# SWD2TC.net
KiCad netlist of a schematic drawn in EAGLE
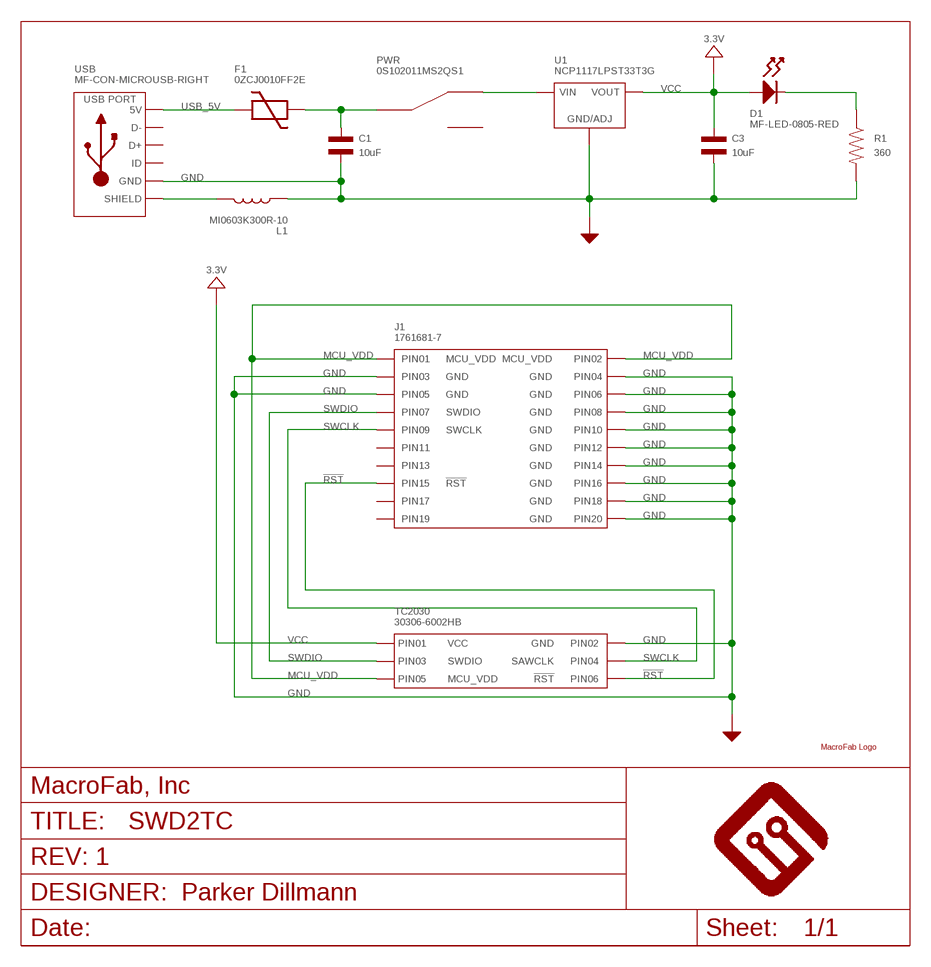
[diagram p0: schematic, sheet 1]

(export (version "E")
  (design (tool "Eeschema 10.0.6"))
  (components
    (comp (ref "C1")
      (value "10uF")
      (footprint "eagle-import:C1206")
      (fields (field (name "MPN") "MF-CAP-1206-10uF"))
      (libsource (lib "eagle-import") (part "CAPACITOR_NP_1206"))
    )
    (comp (ref "C3")
      (value "10uF")
      (footprint "eagle-import:C1206")
      (fields (field (name "MPN") "MF-CAP-1206-10uF"))
      (libsource (lib "eagle-import") (part "CAPACITOR_NP_1206"))
    )
    (comp (ref "D1")
      (value "MF-LED-0805-RED")
      (footprint "eagle-import:LED0805")
      (fields (field (name "HOUSEPART") "YES"))
      (libsource (lib "eagle-import") (part "LED_SINGLE-0805-RED"))
    )
    (comp (ref "F1")
      (value "0ZCJ0010FF2E")
      (footprint "eagle-import:1206")
      (libsource (lib "eagle-import") (part "PTC_FUSE_1206"))
    )
    (comp (ref "FRAME1")
      (value "MF_FRAMEDEFAULT")
      (footprint "eagle-import:MF_FRAME_DEFAULT")
      (fields
        (field (name "HOUSEPART") "0")
        (field (name "DNAME") "Parker Dillmann")
        (field (name "REVNUM") "REV: 1")
      )
      (libsource (lib "eagle-import") (part "MF_FRAMEDEFAULT"))
    )
    (comp (ref "J1")
      (value "1761681-7")
      (footprint "eagle-import:1761681-7")
      (fields
        (field (name "LABEL01") "MCU_VDD")
        (field (name "LABEL02") "MCU_VDD")
        (field (name "LABEL03") "GND")
        (field (name "LABEL04") "GND")
        (field (name "LABEL05") "GND")
        (field (name "LABEL06") "GND")
        (field (name "LABEL07") "SWDIO")
        (field (name "LABEL08") "GND")
        (field (name "LABEL09") "SWCLK")
        (field (name "LABEL10") "GND")
        (field (name "LABEL12") "GND")
        (field (name "LABEL14") "GND")
        (field (name "LABEL15") "!RST")
        (field (name "LABEL16") "GND")
        (field (name "LABEL18") "GND")
        (field (name "LABEL20") "GND")
      )
      (libsource (lib "eagle-import") (part "CON_02X10_1761681-7"))
    )
    (comp (ref "L1")
      (value "MI0603K300R-10")
      (footprint "eagle-import:L0603")
      (fields (field (name "MPN") "MI0603K300R-10"))
      (libsource (lib "eagle-import") (part "INDUCTOR_0603"))
    )
    (comp (ref "PWR")
      (value "0S102011MS2QS1")
      (footprint "eagle-import:0S102011MS2QS1")
      (libsource (lib "eagle-import") (part "SPDT_0S102011MS2QS1"))
    )
    (comp (ref "R1")
      (value "360")
      (footprint "eagle-import:R0805")
      (fields (field (name "MPN") "MF-RES-0805-360"))
      (libsource (lib "eagle-import") (part "RESISTOR_0805"))
    )
    (comp (ref "TC2030")
      (value "30306-6002HB")
      (footprint "eagle-import:30306-6002HB")
      (fields
        (field (name "LABEL01") "VCC")
        (field (name "LABEL02") "GND")
        (field (name "LABEL03") "SWDIO")
        (field (name "LABEL04") "SAWCLK")
        (field (name "LABEL05") "MCU_VDD")
        (field (name "LABEL06") "!RST")
      )
      (libsource (lib "eagle-import") (part "CON_02X03_30306-6002HB"))
    )
    (comp (ref "U$3")
      (value "MF_LOGOLOGO_MEDIUM")
      (footprint "eagle-import:MF_LOGO_MEDIUM")
      (libsource (lib "eagle-import") (part "MF_LOGOLOGO_MEDIUM"))
    )
    (comp (ref "U1")
      (value "NCP1117LPST33T3G")
      (footprint "eagle-import:SOT-223-3")
      (fields (field (name "HOUSEPART") "NO"))
      (libsource (lib "eagle-import") (part "NCP1117LPST33T3G"))
    )
    (comp (ref "USB")
      (value "MF-CON-MICROUSB-RIGHT")
      (footprint "eagle-import:MICROUSB-RIGHT")
      (fields (field (name "HOUSEPART") "YES"))
      (libsource (lib "eagle-import") (part "USB_MICRO_RIGHT"))
    )
  )
  (nets
    (net (code "1") (name "/MCU_VDD") (class "Default")
      (node (ref "J1") (pin "P$1") (pinfunction "1_P$1") (pintype "bidirectional"))
      (node (ref "J1") (pin "P$2") (pinfunction "2_P$2") (pintype "bidirectional"))
      (node (ref "TC2030") (pin "5") (pinfunction "PIN5_5") (pintype "bidirectional"))
    )
    (net (code "2") (name "/SWCLK") (class "Default")
      (node (ref "J1") (pin "P$9") (pinfunction "9_P$9") (pintype "bidirectional"))
      (node (ref "TC2030") (pin "4") (pinfunction "PIN4_4") (pintype "bidirectional"))
    )
    (net (code "3") (name "/SWDIO") (class "Default")
      (node (ref "J1") (pin "P$7") (pinfunction "7_P$7") (pintype "bidirectional"))
      (node (ref "TC2030") (pin "3") (pinfunction "PIN3_3") (pintype "bidirectional"))
    )
    (net (code "4") (name "/USB_5V") (class "Default")
      (node (ref "F1") (pin "1") (pinfunction "P$1_1") (pintype "bidirectional"))
      (node (ref "USB") (pin "1") (pinfunction "5V_1") (pintype "power_in"))
    )
    (net (code "5") (name "/~{RST}") (class "Default")
      (node (ref "J1") (pin "P$15") (pinfunction "15_P$15") (pintype "bidirectional"))
      (node (ref "TC2030") (pin "6") (pinfunction "PIN6_6") (pintype "bidirectional"))
    )
    (net (code "6") (name "3.3V") (class "Default")
      (node (ref "C3") (pin "P$1") (pinfunction "P$1_P$1") (pintype "passive"))
      (node (ref "D1") (pin "ANODE") (pinfunction "ANODE_ANODE") (pintype "power_in"))
      (node (ref "TC2030") (pin "1") (pinfunction "PIN1_1") (pintype "bidirectional"))
      (node (ref "U1") (pin "P$1") (pinfunction "VOUT_P$1") (pintype "bidirectional"))
      (node (ref "U1") (pin "P$3") (pinfunction "VOUT_P$3") (pintype "bidirectional"))
    )
    (net (code "7") (name "GND_RAIL") (class "Default")
      (node (ref "C1") (pin "P$2") (pinfunction "P$2_P$2") (pintype "passive"))
      (node (ref "C3") (pin "P$2") (pinfunction "P$2_P$2") (pintype "passive"))
      (node (ref "J1") (pin "P$10") (pinfunction "10_P$10") (pintype "bidirectional"))
      (node (ref "J1") (pin "P$12") (pinfunction "12_P$12") (pintype "bidirectional"))
      (node (ref "J1") (pin "P$14") (pinfunction "14_P$14") (pintype "bidirectional"))
      (node (ref "J1") (pin "P$16") (pinfunction "16_P$16") (pintype "bidirectional"))
      (node (ref "J1") (pin "P$18") (pinfunction "18_P$18") (pintype "bidirectional"))
      (node (ref "J1") (pin "P$20") (pinfunction "20_P$20") (pintype "bidirectional"))
      (node (ref "J1") (pin "P$3") (pinfunction "3_P$3") (pintype "bidirectional"))
      (node (ref "J1") (pin "P$4") (pinfunction "4_P$4") (pintype "bidirectional"))
      (node (ref "J1") (pin "P$5") (pinfunction "5_P$5") (pintype "bidirectional"))
      (node (ref "J1") (pin "P$6") (pinfunction "6_P$6") (pintype "bidirectional"))
      (node (ref "J1") (pin "P$8") (pinfunction "8_P$8") (pintype "bidirectional"))
      (node (ref "L1") (pin "P$1") (pinfunction "P$1_P$1") (pintype "passive"))
      (node (ref "R1") (pin "P$2") (pinfunction "P$2_P$2") (pintype "passive"))
      (node (ref "TC2030") (pin "2") (pinfunction "PIN2_2") (pintype "bidirectional"))
      (node (ref "U1") (pin "P$2") (pinfunction "GND/ADJ_P$2") (pintype "bidirectional"))
      (node (ref "USB") (pin "5") (pinfunction "GND_5") (pintype "power_in"))
    )
    (net (code "8") (name "Net-(D1-PadCATHODE)") (class "Default")
      (node (ref "D1") (pin "CATHODE") (pinfunction "CATHODE_CATHODE") (pintype "power_in"))
      (node (ref "R1") (pin "P$1") (pinfunction "P$1_P$1") (pintype "passive"))
    )
    (net (code "9") (name "Net-(F1-P$2)") (class "Default")
      (node (ref "C1") (pin "P$1") (pinfunction "P$1_P$1") (pintype "passive"))
      (node (ref "F1") (pin "2") (pinfunction "P$2_2") (pintype "bidirectional"))
      (node (ref "PWR") (pin "2") (pinfunction "C_2") (pintype "bidirectional"))
    )
    (net (code "10") (name "Net-(L1-PadP$2)") (class "Default")
      (node (ref "L1") (pin "P$2") (pinfunction "P$2_P$2") (pintype "passive"))
      (node (ref "USB") (pin "S1") (pinfunction "SLD_S1") (pintype "power_in"))
      (node (ref "USB") (pin "S2") (pinfunction "SLD_S2") (pintype "power_in"))
      (node (ref "USB") (pin "S3") (pinfunction "SLD_S3") (pintype "power_in"))
      (node (ref "USB") (pin "S4") (pinfunction "SLD_S4") (pintype "power_in"))
      (node (ref "USB") (pin "S5") (pinfunction "SLD_S5") (pintype "power_in"))
      (node (ref "USB") (pin "S6") (pinfunction "SLD_S6") (pintype "power_in"))
    )
    (net (code "11") (name "Net-(U1-VIN)") (class "Default")
      (node (ref "PWR") (pin "1") (pinfunction "1_1") (pintype "bidirectional"))
      (node (ref "U1") (pin "P$4") (pinfunction "VIN_P$4") (pintype "bidirectional"))
    )
    (net (code "12") (name "unconnected-(J1-11-PadP$11)") (class "Default")
      (node (ref "J1") (pin "P$11") (pinfunction "11_P$11") (pintype "bidirectional"))
    )
    (net (code "13") (name "unconnected-(J1-13-PadP$13)") (class "Default")
      (node (ref "J1") (pin "P$13") (pinfunction "13_P$13") (pintype "bidirectional"))
    )
    (net (code "14") (name "unconnected-(J1-17-PadP$17)") (class "Default")
      (node (ref "J1") (pin "P$17") (pinfunction "17_P$17") (pintype "bidirectional"))
    )
    (net (code "15") (name "unconnected-(J1-19-PadP$19)") (class "Default")
      (node (ref "J1") (pin "P$19") (pinfunction "19_P$19") (pintype "bidirectional"))
    )
    (net (code "16") (name "unconnected-(PWR-2-Pad3)") (class "Default")
      (node (ref "PWR") (pin "3") (pinfunction "2_3") (pintype "bidirectional"))
    )
    (net (code "17") (name "unconnected-(USB-D+-Pad3)") (class "Default")
      (node (ref "USB") (pin "3") (pinfunction "D+_3") (pintype "bidirectional"))
    )
    (net (code "18") (name "unconnected-(USB-D--Pad2)") (class "Default")
      (node (ref "USB") (pin "2") (pinfunction "D-_2") (pintype "bidirectional"))
    )
    (net (code "19") (name "unconnected-(USB-ID-Pad4)") (class "Default")
      (node (ref "USB") (pin "4") (pinfunction "ID_4") (pintype "bidirectional"))
    )
  )
)
